# h_bridge1.net
KiCad netlist of a schematic drawn in EAGLE
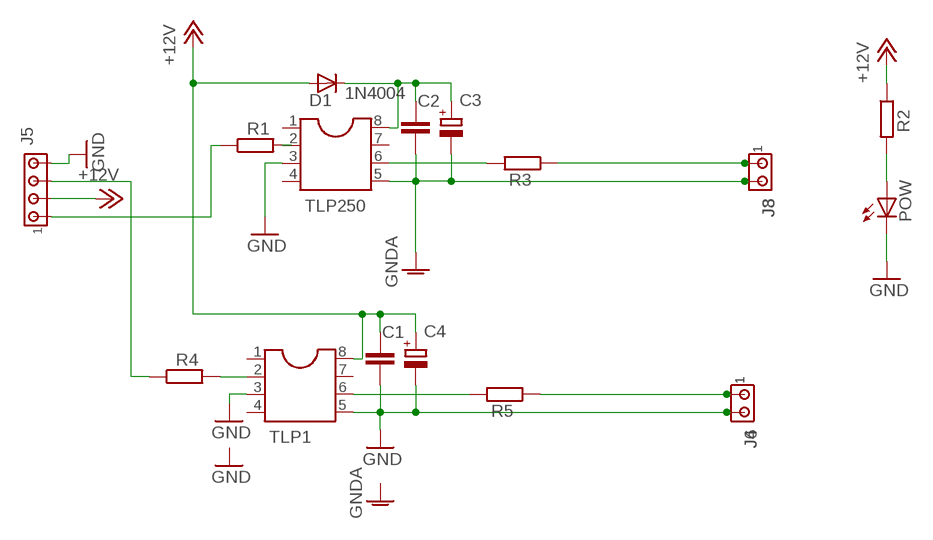
[diagram p0: schematic, sheet 1]
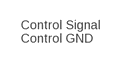
[diagram p1: schematic, sheet 2]

(export (version "E")
  (design (tool "Eeschema 10.0.6"))
  (components
    (comp (ref "C1")
      (value "C-EU025-025X050")
      (footprint "eagle-import:C025-025X050")
      (libsource (lib "eagle-import") (part "C-EU025-025X050"))
    )
    (comp (ref "C2")
      (value "C-EU025-025X050")
      (footprint "eagle-import:C025-025X050")
      (libsource (lib "eagle-import") (part "C-EU025-025X050"))
    )
    (comp (ref "C3")
      (value "CPOL-EUE2.5-6")
      (footprint "eagle-import:E2,5-6")
      (libsource (lib "eagle-import") (part "CPOL-EUE2.5-6"))
    )
    (comp (ref "C4")
      (value "CPOL-EUE2.5-6")
      (footprint "eagle-import:E2,5-6")
      (libsource (lib "eagle-import") (part "CPOL-EUE2.5-6"))
    )
    (comp (ref "D1")
      (value "1N4004")
      (footprint "eagle-import:DO41-10")
      (libsource (lib "eagle-import") (part "1N4004"))
    )
    (comp (ref "J3")
      (value "MTA02-100")
      (footprint "eagle-import:10X02MTA")
      (libsource (lib "eagle-import") (part "MTA02-100"))
    )
    (comp (ref "J4")
      (value "MTA02-100")
      (footprint "eagle-import:10X02MTA")
      (libsource (lib "eagle-import") (part "MTA02-100"))
    )
    (comp (ref "J5")
      (value "MTA04-100")
      (footprint "eagle-import:10X04MTA")
      (libsource (lib "eagle-import") (part "MTA04-100"))
    )
    (comp (ref "J6")
      (value "MTA02-100")
      (footprint "eagle-import:10X02MTA")
      (libsource (lib "eagle-import") (part "MTA02-100"))
    )
    (comp (ref "J8")
      (value "MTA02-100")
      (footprint "eagle-import:10X02MTA")
      (libsource (lib "eagle-import") (part "MTA02-100"))
    )
    (comp (ref "POW")
      (value "LED3MM")
      (footprint "eagle-import:LED3MM")
      (libsource (lib "eagle-import") (part "LED3MM"))
    )
    (comp (ref "R1")
      (value "R-EU_0204/7")
      (footprint "eagle-import:0204_7")
      (libsource (lib "eagle-import") (part "R-EU_0204/7"))
    )
    (comp (ref "R2")
      (value "R-EU_0204/7")
      (footprint "eagle-import:0204_7")
      (libsource (lib "eagle-import") (part "R-EU_0204/7"))
    )
    (comp (ref "R3")
      (value "R-EU_0204/7")
      (footprint "eagle-import:0204_7")
      (libsource (lib "eagle-import") (part "R-EU_0204/7"))
    )
    (comp (ref "R4")
      (value "R-EU_0204/7")
      (footprint "eagle-import:0204_7")
      (libsource (lib "eagle-import") (part "R-EU_0204/7"))
    )
    (comp (ref "R5")
      (value "R-EU_0204/7")
      (footprint "eagle-import:0204_7")
      (libsource (lib "eagle-import") (part "R-EU_0204/7"))
    )
    (comp (ref "TLP1")
      (value "DIL8")
      (footprint "eagle-import:DIL08")
      (libsource (lib "eagle-import") (part "DIL8"))
    )
    (comp (ref "TLP250")
      (value "DIL8")
      (footprint "eagle-import:DIL08")
      (libsource (lib "eagle-import") (part "DIL8"))
    )
  )
  (nets
    (net (code "1") (name "+12V") (class "Default")
      (node (ref "C1") (pin "1") (pinfunction "1_1") (pintype "passive"))
      (node (ref "C4") (pin "+") (pinfunction "+_+") (pintype "passive"))
      (node (ref "D1") (pin "A") (pinfunction "A_A") (pintype "passive"))
      (node (ref "J5") (pin "2") (pinfunction "2_2") (pintype "passive"))
      (node (ref "R2") (pin "1") (pinfunction "1_1") (pintype "passive"))
      (node (ref "TLP1") (pin "8") (pinfunction "8_8") (pintype "passive"))
    )
    (net (code "2") (name "GND") (class "Default")
      (node (ref "C1") (pin "2") (pinfunction "2_2") (pintype "passive"))
      (node (ref "C4") (pin "-") (pinfunction "-_-") (pintype "passive"))
      (node (ref "J4") (pin "2") (pinfunction "2_2") (pintype "passive"))
      (node (ref "J5") (pin "4") (pinfunction "4_4") (pintype "passive"))
      (node (ref "J6") (pin "2") (pinfunction "2_2") (pintype "passive"))
      (node (ref "POW") (pin "K") (pinfunction "C_K") (pintype "passive"))
      (node (ref "TLP1") (pin "3") (pinfunction "3_3") (pintype "passive"))
      (node (ref "TLP1") (pin "5") (pinfunction "5_5") (pintype "passive"))
      (node (ref "TLP250") (pin "3") (pinfunction "3_3") (pintype "passive"))
    )
    (net (code "3") (name "GNDA") (class "Default")
      (node (ref "C2") (pin "2") (pinfunction "2_2") (pintype "passive"))
      (node (ref "C3") (pin "-") (pinfunction "-_-") (pintype "passive"))
      (node (ref "J3") (pin "2") (pinfunction "2_2") (pintype "passive"))
      (node (ref "J8") (pin "2") (pinfunction "2_2") (pintype "passive"))
      (node (ref "TLP250") (pin "5") (pinfunction "5_5") (pintype "passive"))
    )
    (net (code "4") (name "Net-(C2-Pad1)") (class "Default")
      (node (ref "C2") (pin "1") (pinfunction "1_1") (pintype "passive"))
      (node (ref "C3") (pin "+") (pinfunction "+_+") (pintype "passive"))
      (node (ref "D1") (pin "C") (pinfunction "C_C") (pintype "passive"))
      (node (ref "TLP250") (pin "8") (pinfunction "8_8") (pintype "passive"))
    )
    (net (code "5") (name "Net-(J3-Pad1)") (class "Default")
      (node (ref "J3") (pin "1") (pinfunction "1_1") (pintype "passive"))
      (node (ref "J8") (pin "1") (pinfunction "1_1") (pintype "passive"))
      (node (ref "R3") (pin "1") (pinfunction "1_1") (pintype "passive"))
    )
    (net (code "6") (name "Net-(J4-Pad1)") (class "Default")
      (node (ref "J4") (pin "1") (pinfunction "1_1") (pintype "passive"))
      (node (ref "J6") (pin "1") (pinfunction "1_1") (pintype "passive"))
      (node (ref "R5") (pin "1") (pinfunction "1_1") (pintype "passive"))
    )
    (net (code "7") (name "Net-(J5-Pad1)") (class "Default")
      (node (ref "J5") (pin "1") (pinfunction "1_1") (pintype "passive"))
      (node (ref "R1") (pin "1") (pinfunction "1_1") (pintype "passive"))
    )
    (net (code "8") (name "Net-(J5-Pad3)") (class "Default")
      (node (ref "J5") (pin "3") (pinfunction "3_3") (pintype "passive"))
      (node (ref "R4") (pin "1") (pinfunction "1_1") (pintype "passive"))
    )
    (net (code "9") (name "Net-(POW-PadA)") (class "Default")
      (node (ref "POW") (pin "A") (pinfunction "A_A") (pintype "passive"))
      (node (ref "R2") (pin "2") (pinfunction "2_2") (pintype "passive"))
    )
    (net (code "10") (name "Net-(R1-Pad2)") (class "Default")
      (node (ref "R1") (pin "2") (pinfunction "2_2") (pintype "passive"))
      (node (ref "TLP250") (pin "2") (pinfunction "2_2") (pintype "passive"))
    )
    (net (code "11") (name "Net-(R3-Pad2)") (class "Default")
      (node (ref "R3") (pin "2") (pinfunction "2_2") (pintype "passive"))
      (node (ref "TLP250") (pin "6") (pinfunction "6_6") (pintype "passive"))
    )
    (net (code "12") (name "Net-(R4-Pad2)") (class "Default")
      (node (ref "R4") (pin "2") (pinfunction "2_2") (pintype "passive"))
      (node (ref "TLP1") (pin "2") (pinfunction "2_2") (pintype "passive"))
    )
    (net (code "13") (name "Net-(R5-Pad2)") (class "Default")
      (node (ref "R5") (pin "2") (pinfunction "2_2") (pintype "passive"))
      (node (ref "TLP1") (pin "6") (pinfunction "6_6") (pintype "passive"))
    )
    (net (code "14") (name "unconnected-(TLP1-Pad1)") (class "Default")
      (node (ref "TLP1") (pin "1") (pinfunction "1_1") (pintype "passive"))
    )
    (net (code "15") (name "unconnected-(TLP1-Pad4)") (class "Default")
      (node (ref "TLP1") (pin "4") (pinfunction "4_4") (pintype "passive"))
    )
    (net (code "16") (name "unconnected-(TLP1-Pad7)") (class "Default")
      (node (ref "TLP1") (pin "7") (pinfunction "7_7") (pintype "passive"))
    )
    (net (code "17") (name "unconnected-(TLP250-Pad1)") (class "Default")
      (node (ref "TLP250") (pin "1") (pinfunction "1_1") (pintype "passive"))
    )
    (net (code "18") (name "unconnected-(TLP250-Pad4)") (class "Default")
      (node (ref "TLP250") (pin "4") (pinfunction "4_4") (pintype "passive"))
    )
    (net (code "19") (name "unconnected-(TLP250-Pad7)") (class "Default")
      (node (ref "TLP250") (pin "7") (pinfunction "7_7") (pintype "passive"))
    )
  )
)
